# 06_MCU_Part3.net
KiCad netlist of a schematic drawn in Altium Designer
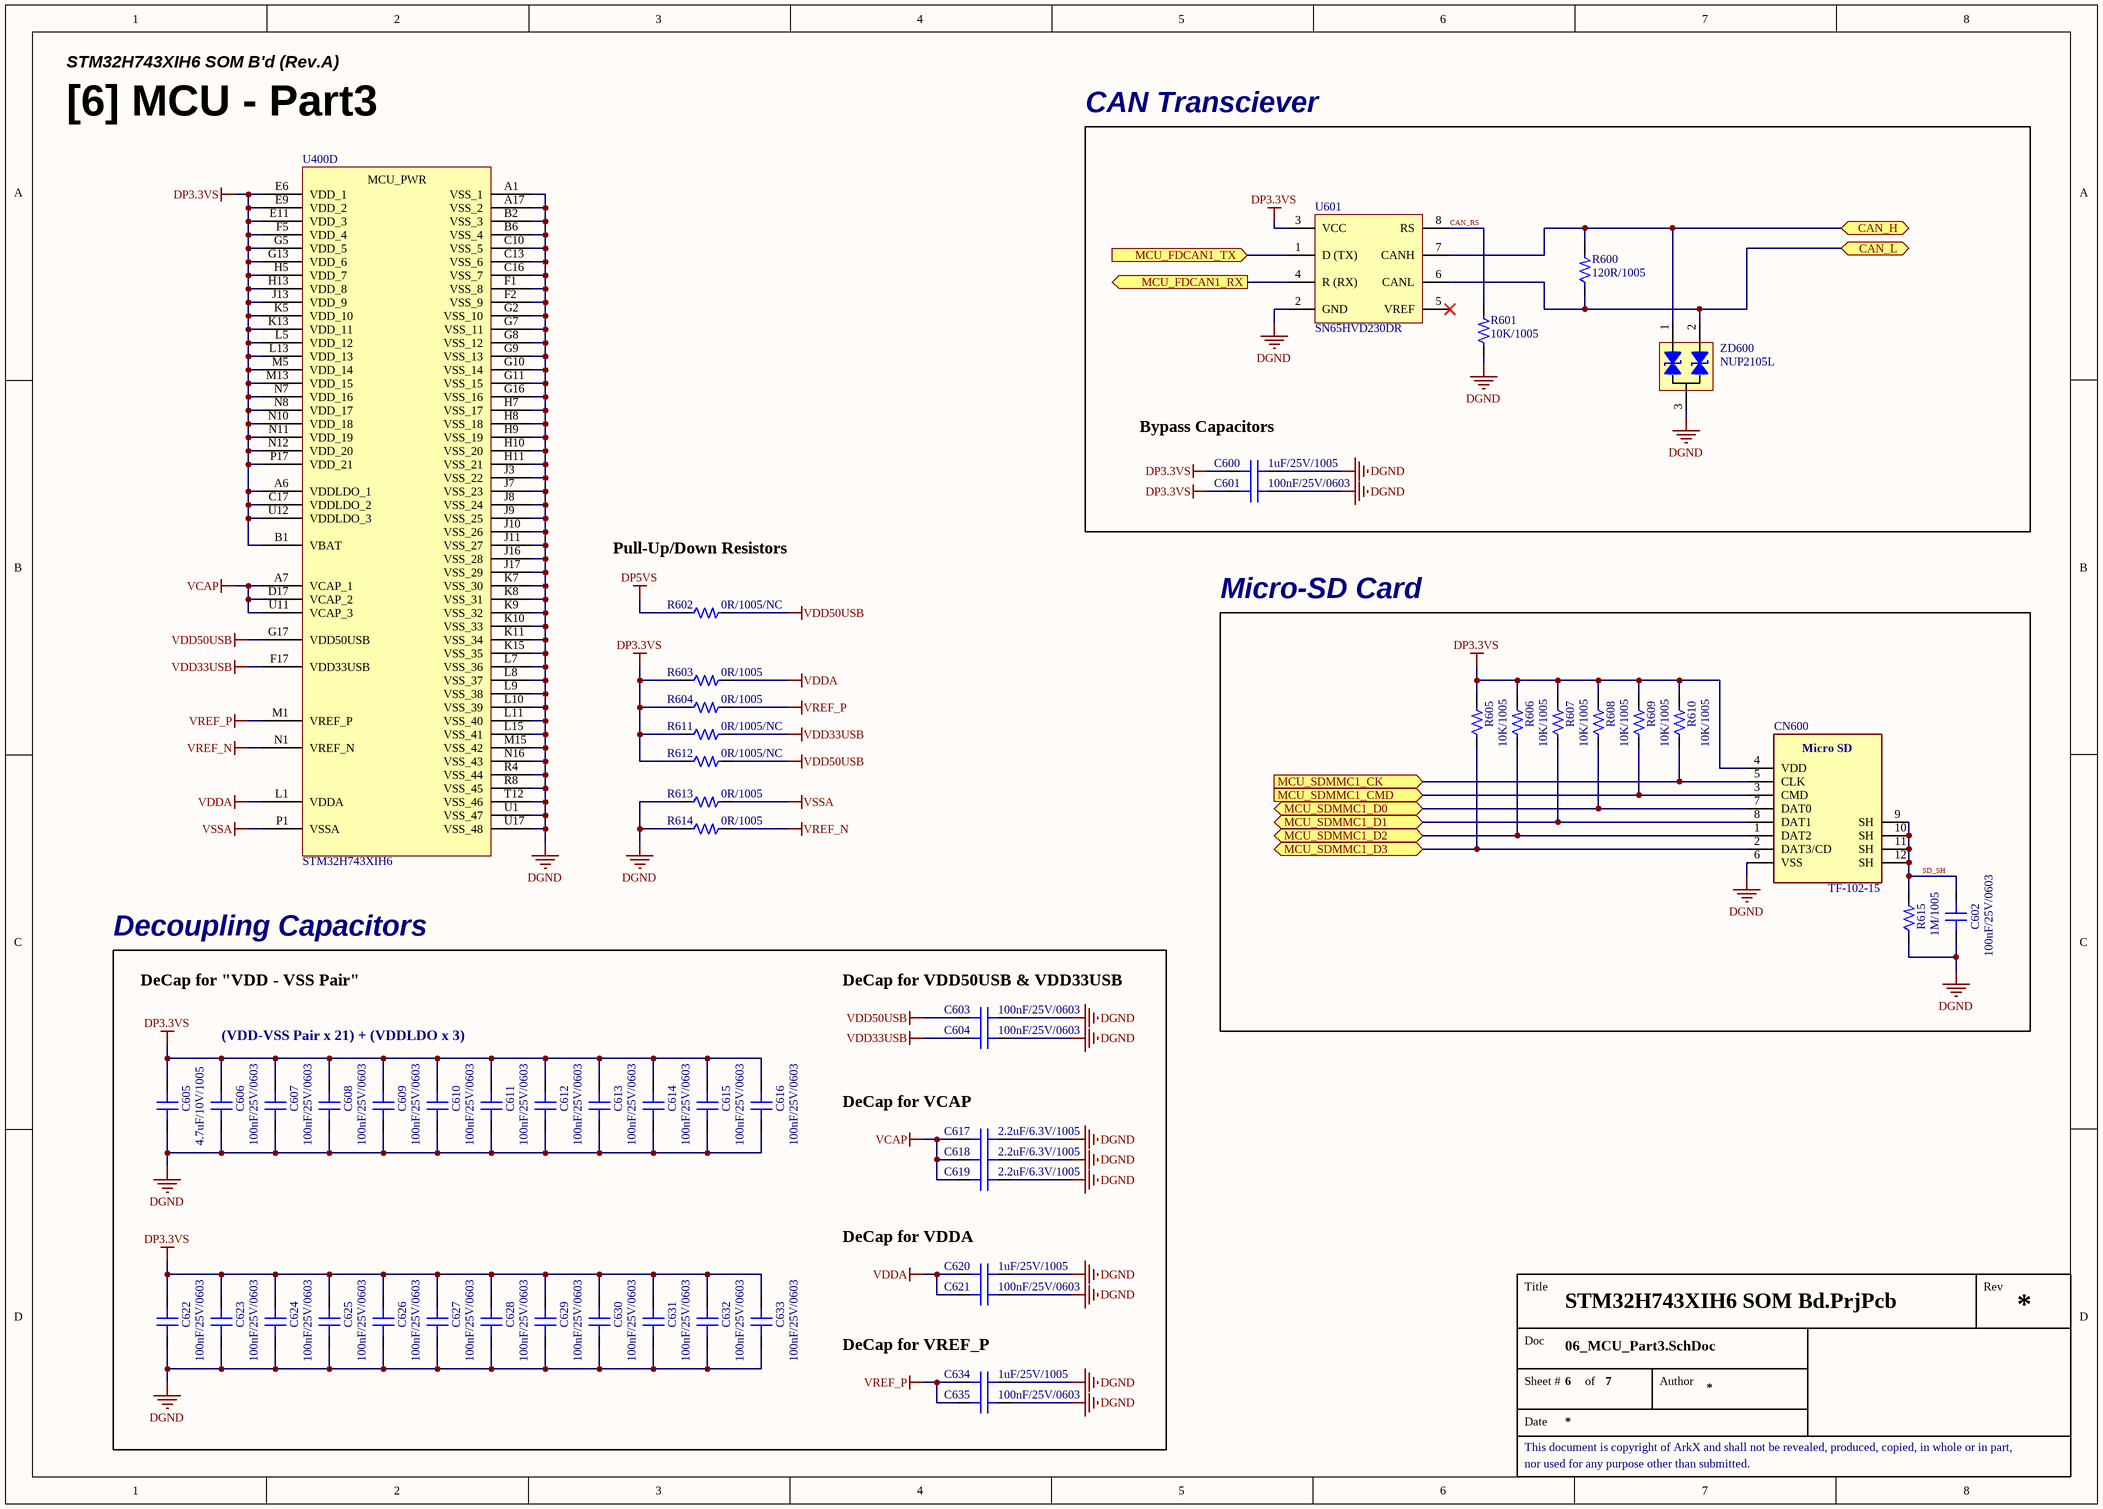
[diagram p0: 06_MCU_Part3.SchDoc]

(export (version "E")
  (design (tool "Eeschema 10.0.6"))
  (components
    (comp (ref "C600")
      (value "1uF/25V/1005")
      (footprint "CAP 1005 (0402_INCH)")
      (description "Ceramic CAP_1uF/25V/1005")
      (fields (field (name "LCSC PART #") "C52923"))
      (libsource (lib "Arkx") (part "CAP_1uF/25V/1005"))
    )
    (comp (ref "C601")
      (value "100nF/25V/0603")
      (footprint "CAP 0603 (0201_INCH)")
      (description "Ceramic CAP_100nF/25V/0603")
      (fields (field (name "LCSC PART #") "C181047"))
      (libsource (lib "Arkx") (part "CAP_100nF/25V/0603"))
    )
    (comp (ref "C602")
      (value "100nF/25V/0603")
      (footprint "CAP 0603 (0201_INCH)")
      (description "Ceramic CAP_100nF/25V/0603")
      (fields (field (name "LCSC PART #") "C181047"))
      (libsource (lib "Arkx") (part "CAP_100nF/25V/0603"))
    )
    (comp (ref "C603")
      (value "100nF/25V/0603")
      (footprint "CAP 0603 (0201_INCH)")
      (description "Ceramic CAP_100nF/25V/0603")
      (fields (field (name "LCSC PART #") "C181047"))
      (libsource (lib "Arkx") (part "CAP_100nF/25V/0603"))
    )
    (comp (ref "C604")
      (value "100nF/25V/0603")
      (footprint "CAP 0603 (0201_INCH)")
      (description "Ceramic CAP_100nF/25V/0603")
      (fields (field (name "LCSC PART #") "C181047"))
      (libsource (lib "Arkx") (part "CAP_100nF/25V/0603"))
    )
    (comp (ref "C605")
      (value "4.7uF/10V/1005")
      (footprint "CAP 1005 (0402_INCH)")
      (description "10V 4.7uF X5R ±20% 0402  Multilayer Ceramic Capacitors MLCC - SMD/SMT ROHS")
      (fields (field (name "LCSC PART #") "C23733"))
      (libsource (lib "Arkx") (part "CAP_4.7uF/10V/1005"))
    )
    (comp (ref "C606")
      (value "100nF/25V/0603")
      (footprint "CAP 0603 (0201_INCH)")
      (description "Ceramic CAP_100nF/25V/0603")
      (fields (field (name "LCSC PART #") "C181047"))
      (libsource (lib "Arkx") (part "CAP_100nF/25V/0603"))
    )
    (comp (ref "C607")
      (value "100nF/25V/0603")
      (footprint "CAP 0603 (0201_INCH)")
      (description "Ceramic CAP_100nF/25V/0603")
      (fields (field (name "LCSC PART #") "C181047"))
      (libsource (lib "Arkx") (part "CAP_100nF/25V/0603"))
    )
    (comp (ref "C608")
      (value "100nF/25V/0603")
      (footprint "CAP 0603 (0201_INCH)")
      (description "Ceramic CAP_100nF/25V/0603")
      (fields (field (name "LCSC PART #") "C181047"))
      (libsource (lib "Arkx") (part "CAP_100nF/25V/0603"))
    )
    (comp (ref "C609")
      (value "100nF/25V/0603")
      (footprint "CAP 0603 (0201_INCH)")
      (description "Ceramic CAP_100nF/25V/0603")
      (fields (field (name "LCSC PART #") "C181047"))
      (libsource (lib "Arkx") (part "CAP_100nF/25V/0603"))
    )
    (comp (ref "C610")
      (value "100nF/25V/0603")
      (footprint "CAP 0603 (0201_INCH)")
      (description "Ceramic CAP_100nF/25V/0603")
      (fields (field (name "LCSC PART #") "C181047"))
      (libsource (lib "Arkx") (part "CAP_100nF/25V/0603"))
    )
    (comp (ref "C611")
      (value "100nF/25V/0603")
      (footprint "CAP 0603 (0201_INCH)")
      (description "Ceramic CAP_100nF/25V/0603")
      (fields (field (name "LCSC PART #") "C181047"))
      (libsource (lib "Arkx") (part "CAP_100nF/25V/0603"))
    )
    (comp (ref "C612")
      (value "100nF/25V/0603")
      (footprint "CAP 0603 (0201_INCH)")
      (description "Ceramic CAP_100nF/25V/0603")
      (fields (field (name "LCSC PART #") "C181047"))
      (libsource (lib "Arkx") (part "CAP_100nF/25V/0603"))
    )
    (comp (ref "C613")
      (value "100nF/25V/0603")
      (footprint "CAP 0603 (0201_INCH)")
      (description "Ceramic CAP_100nF/25V/0603")
      (fields (field (name "LCSC PART #") "C181047"))
      (libsource (lib "Arkx") (part "CAP_100nF/25V/0603"))
    )
    (comp (ref "C614")
      (value "100nF/25V/0603")
      (footprint "CAP 0603 (0201_INCH)")
      (description "Ceramic CAP_100nF/25V/0603")
      (fields (field (name "LCSC PART #") "C181047"))
      (libsource (lib "Arkx") (part "CAP_100nF/25V/0603"))
    )
    (comp (ref "C615")
      (value "100nF/25V/0603")
      (footprint "CAP 0603 (0201_INCH)")
      (description "Ceramic CAP_100nF/25V/0603")
      (fields (field (name "LCSC PART #") "C181047"))
      (libsource (lib "Arkx") (part "CAP_100nF/25V/0603"))
    )
    (comp (ref "C616")
      (value "100nF/25V/0603")
      (footprint "CAP 0603 (0201_INCH)")
      (description "Ceramic CAP_100nF/25V/0603")
      (fields (field (name "LCSC PART #") "C181047"))
      (libsource (lib "Arkx") (part "CAP_100nF/25V/0603"))
    )
    (comp (ref "C617")
      (value "2.2uF/6.3V/1005")
      (footprint "CAP 1005 (0402_INCH)")
      (description "Ceramic CAP_2.2uF/6.3V/1005")
      (fields (field (name "LCSC PART #") "C12530"))
      (libsource (lib "Arkx") (part "CAP_2.2uF/6.3V/1005"))
    )
    (comp (ref "C618")
      (value "2.2uF/6.3V/1005")
      (footprint "CAP 1005 (0402_INCH)")
      (description "Ceramic CAP_2.2uF/6.3V/1005")
      (fields (field (name "LCSC PART #") "C12530"))
      (libsource (lib "Arkx") (part "CAP_2.2uF/6.3V/1005"))
    )
    (comp (ref "C619")
      (value "2.2uF/6.3V/1005")
      (footprint "CAP 1005 (0402_INCH)")
      (description "Ceramic CAP_2.2uF/6.3V/1005")
      (fields (field (name "LCSC PART #") "C12530"))
      (libsource (lib "Arkx") (part "CAP_2.2uF/6.3V/1005"))
    )
    (comp (ref "C620")
      (value "1uF/25V/1005")
      (footprint "CAP 1005 (0402_INCH)")
      (description "Ceramic CAP_1uF/25V/1005")
      (fields (field (name "LCSC PART #") "C52923"))
      (libsource (lib "Arkx") (part "CAP_1uF/25V/1005"))
    )
    (comp (ref "C621")
      (value "100nF/25V/0603")
      (footprint "CAP 0603 (0201_INCH)")
      (description "Ceramic CAP_100nF/25V/0603")
      (fields (field (name "LCSC PART #") "C181047"))
      (libsource (lib "Arkx") (part "CAP_100nF/25V/0603"))
    )
    (comp (ref "C622")
      (value "100nF/25V/0603")
      (footprint "CAP 0603 (0201_INCH)")
      (description "Ceramic CAP_100nF/25V/0603")
      (fields (field (name "LCSC PART #") "C181047"))
      (libsource (lib "Arkx") (part "CAP_100nF/25V/0603"))
    )
    (comp (ref "C623")
      (value "100nF/25V/0603")
      (footprint "CAP 0603 (0201_INCH)")
      (description "Ceramic CAP_100nF/25V/0603")
      (fields (field (name "LCSC PART #") "C181047"))
      (libsource (lib "Arkx") (part "CAP_100nF/25V/0603"))
    )
    (comp (ref "C624")
      (value "100nF/25V/0603")
      (footprint "CAP 0603 (0201_INCH)")
      (description "Ceramic CAP_100nF/25V/0603")
      (fields (field (name "LCSC PART #") "C181047"))
      (libsource (lib "Arkx") (part "CAP_100nF/25V/0603"))
    )
    (comp (ref "C625")
      (value "100nF/25V/0603")
      (footprint "CAP 0603 (0201_INCH)")
      (description "Ceramic CAP_100nF/25V/0603")
      (fields (field (name "LCSC PART #") "C181047"))
      (libsource (lib "Arkx") (part "CAP_100nF/25V/0603"))
    )
    (comp (ref "C626")
      (value "100nF/25V/0603")
      (footprint "CAP 0603 (0201_INCH)")
      (description "Ceramic CAP_100nF/25V/0603")
      (fields (field (name "LCSC PART #") "C181047"))
      (libsource (lib "Arkx") (part "CAP_100nF/25V/0603"))
    )
    (comp (ref "C627")
      (value "100nF/25V/0603")
      (footprint "CAP 0603 (0201_INCH)")
      (description "Ceramic CAP_100nF/25V/0603")
      (fields (field (name "LCSC PART #") "C181047"))
      (libsource (lib "Arkx") (part "CAP_100nF/25V/0603"))
    )
    (comp (ref "C628")
      (value "100nF/25V/0603")
      (footprint "CAP 0603 (0201_INCH)")
      (description "Ceramic CAP_100nF/25V/0603")
      (fields (field (name "LCSC PART #") "C181047"))
      (libsource (lib "Arkx") (part "CAP_100nF/25V/0603"))
    )
    (comp (ref "C629")
      (value "100nF/25V/0603")
      (footprint "CAP 0603 (0201_INCH)")
      (description "Ceramic CAP_100nF/25V/0603")
      (fields (field (name "LCSC PART #") "C181047"))
      (libsource (lib "Arkx") (part "CAP_100nF/25V/0603"))
    )
    (comp (ref "C630")
      (value "100nF/25V/0603")
      (footprint "CAP 0603 (0201_INCH)")
      (description "Ceramic CAP_100nF/25V/0603")
      (fields (field (name "LCSC PART #") "C181047"))
      (libsource (lib "Arkx") (part "CAP_100nF/25V/0603"))
    )
    (comp (ref "C631")
      (value "100nF/25V/0603")
      (footprint "CAP 0603 (0201_INCH)")
      (description "Ceramic CAP_100nF/25V/0603")
      (fields (field (name "LCSC PART #") "C181047"))
      (libsource (lib "Arkx") (part "CAP_100nF/25V/0603"))
    )
    (comp (ref "C632")
      (value "100nF/25V/0603")
      (footprint "CAP 0603 (0201_INCH)")
      (description "Ceramic CAP_100nF/25V/0603")
      (fields (field (name "LCSC PART #") "C181047"))
      (libsource (lib "Arkx") (part "CAP_100nF/25V/0603"))
    )
    (comp (ref "C633")
      (value "100nF/25V/0603")
      (footprint "CAP 0603 (0201_INCH)")
      (description "Ceramic CAP_100nF/25V/0603")
      (fields (field (name "LCSC PART #") "C181047"))
      (libsource (lib "Arkx") (part "CAP_100nF/25V/0603"))
    )
    (comp (ref "C634")
      (value "1uF/25V/1005")
      (footprint "CAP 1005 (0402_INCH)")
      (description "Ceramic CAP_1uF/25V/1005")
      (fields (field (name "LCSC PART #") "C52923"))
      (libsource (lib "Arkx") (part "CAP_1uF/25V/1005"))
    )
    (comp (ref "C635")
      (value "100nF/25V/0603")
      (footprint "CAP 0603 (0201_INCH)")
      (description "Ceramic CAP_100nF/25V/0603")
      (fields (field (name "LCSC PART #") "C181047"))
      (libsource (lib "Arkx") (part "CAP_100nF/25V/0603"))
    )
    (comp (ref "CN600")
      (value "TF-102-15")
      (footprint "CON_MICRO-SD_Socket_TF-102-15")
      (fields (field (name "LCSC PART #") "C266609"))
      (libsource (lib "Arkx") (part "CON_MICRO-SD_Socket_TF-102-15"))
    )
    (comp (ref "R600")
      (value "120R/1005")
      (footprint "RES 1005 (0402_inch)")
      (description "RES_120R/1005/62.5mW")
      (fields (field (name "LCSC PART #") "C25079"))
      (libsource (lib "Arkx") (part "RES_120R/1005/62.5mW"))
    )
    (comp (ref "R601")
      (value "10K/1005")
      (footprint "RES 1005 (0402_inch)")
      (description "RES_10K/1005/62.5mW")
      (fields (field (name "LCSC PART #") "C25744"))
      (libsource (lib "Arkx") (part "RES_10K/1005/62.5mW"))
    )
    (comp (ref "R602")
      (value "0R/1005/NC")
      (footprint "RES 1005 (0402_inch)/NC")
      (description "RES_0R/1005/62.5mW/NC")
      (libsource (lib "Arkx") (part "RES_NC_0R/1005/62.5mW"))
    )
    (comp (ref "R603")
      (value "0R/1005")
      (footprint "RES 1005 (0402_inch)")
      (description "RES_0R/1005/62.5mW")
      (fields (field (name "LCSC PART #") "C17168"))
      (libsource (lib "Arkx") (part "RES_0R/1005/62.5mW"))
    )
    (comp (ref "R604")
      (value "0R/1005")
      (footprint "RES 1005 (0402_inch)")
      (description "RES_0R/1005/62.5mW")
      (fields (field (name "LCSC PART #") "C17168"))
      (libsource (lib "Arkx") (part "RES_0R/1005/62.5mW"))
    )
    (comp (ref "R605")
      (value "10K/1005")
      (footprint "RES 1005 (0402_inch)")
      (description "RES_10K/1005/62.5mW")
      (fields (field (name "LCSC PART #") "C25744"))
      (libsource (lib "Arkx") (part "RES_10K/1005/62.5mW"))
    )
    (comp (ref "R606")
      (value "10K/1005")
      (footprint "RES 1005 (0402_inch)")
      (description "RES_10K/1005/62.5mW")
      (fields (field (name "LCSC PART #") "C25744"))
      (libsource (lib "Arkx") (part "RES_10K/1005/62.5mW"))
    )
    (comp (ref "R607")
      (value "10K/1005")
      (footprint "RES 1005 (0402_inch)")
      (description "RES_10K/1005/62.5mW")
      (fields (field (name "LCSC PART #") "C25744"))
      (libsource (lib "Arkx") (part "RES_10K/1005/62.5mW"))
    )
    (comp (ref "R608")
      (value "10K/1005")
      (footprint "RES 1005 (0402_inch)")
      (description "RES_10K/1005/62.5mW")
      (fields (field (name "LCSC PART #") "C25744"))
      (libsource (lib "Arkx") (part "RES_10K/1005/62.5mW"))
    )
    (comp (ref "R609")
      (value "10K/1005")
      (footprint "RES 1005 (0402_inch)")
      (description "RES_10K/1005/62.5mW")
      (fields (field (name "LCSC PART #") "C25744"))
      (libsource (lib "Arkx") (part "RES_10K/1005/62.5mW"))
    )
    (comp (ref "R610")
      (value "10K/1005")
      (footprint "RES 1005 (0402_inch)")
      (description "RES_10K/1005/62.5mW")
      (fields (field (name "LCSC PART #") "C25744"))
      (libsource (lib "Arkx") (part "RES_10K/1005/62.5mW"))
    )
    (comp (ref "R611")
      (value "0R/1005/NC")
      (footprint "RES 1005 (0402_inch)/NC")
      (description "RES_0R/1005/62.5mW/NC")
      (libsource (lib "Arkx") (part "RES_NC_0R/1005/62.5mW"))
    )
    (comp (ref "R612")
      (value "0R/1005/NC")
      (footprint "RES 1005 (0402_inch)/NC")
      (description "RES_0R/1005/62.5mW/NC")
      (libsource (lib "Arkx") (part "RES_NC_0R/1005/62.5mW"))
    )
    (comp (ref "R613")
      (value "0R/1005")
      (footprint "RES 1005 (0402_inch)")
      (description "RES_0R/1005/62.5mW")
      (fields (field (name "LCSC PART #") "C17168"))
      (libsource (lib "Arkx") (part "RES_0R/1005/62.5mW"))
    )
    (comp (ref "R614")
      (value "0R/1005")
      (footprint "RES 1005 (0402_inch)")
      (description "RES_0R/1005/62.5mW")
      (fields (field (name "LCSC PART #") "C17168"))
      (libsource (lib "Arkx") (part "RES_0R/1005/62.5mW"))
    )
    (comp (ref "R615")
      (value "1M/1005")
      (footprint "RES 1005 (0402_inch)")
      (description "RES_1M/1005/62.5mW")
      (fields (field (name "LCSC PART #") "C26083"))
      (libsource (lib "Arkx") (part "RES_1M/1005/62.5mW"))
    )
    (comp (ref "U400")
      (value "STM32H743XIH6")
      (footprint "IC TFBGA-265")
      (description "ARM® Cortex®-M7 STM32H7 MCU IC 32bit Single-core 480MHz 2MB(2M x 8) Flash 240+25-TFBGA(14x14)")
      (fields (field (name "LCSC PART #") "C114407"))
      (libsource (lib "Arkx") (part "IC_MCU_STM32H743XIH6"))
    )
    (comp (ref "U601")
      (value "SN65HVD230DR")
      (footprint "SOIC-8 R8 (ANALOG DEV)")
      (description "IC TRANSCEIVER HALF 1/1 8SOIC")
      (fields (field (name "LCSC PART #") "C12084"))
      (libsource (lib "Arkx") (part "IC_CAN_SN65HVD230DR"))
    )
    (comp (ref "ZD600")
      (value "NUP2105L")
      (footprint "SOT 23-3 (DIODES INCORPORATED)")
      (description "SOT-23 ESD PROTECTION DEVICES RO")
      (fields (field (name "LCSC PART #") "C5158054"))
      (libsource (lib "Arkx") (part "DIO_TVS_NUP2105L"))
    )
  )
  (nets
    (net (code "1") (name "/CAN_H") (class "Default")
      (node (ref "R600") (pin "2") (pinfunction "2_2") (pintype "passive"))
      (node (ref "U601") (pin "7") (pinfunction "CANH_7") (pintype "passive"))
      (node (ref "ZD600") (pin "1") (pinfunction "CANH_1") (pintype "passive"))
    )
    (net (code "2") (name "/CAN_L") (class "Default")
      (node (ref "R600") (pin "1") (pinfunction "1_1") (pintype "passive"))
      (node (ref "U601") (pin "6") (pinfunction "CANL_6") (pintype "passive"))
      (node (ref "ZD600") (pin "2") (pinfunction "CANL_2") (pintype "passive"))
    )
    (net (code "3") (name "/CAN_RS") (class "Default")
      (node (ref "R601") (pin "2") (pinfunction "2_2") (pintype "passive"))
      (node (ref "U601") (pin "8") (pinfunction "RS_8") (pintype "passive"))
    )
    (net (code "4") (name "/MCU_FDCAN1_RX") (class "Default")
      (node (ref "U601") (pin "4") (pinfunction "R_(RX)_4") (pintype "passive"))
    )
    (net (code "5") (name "/MCU_FDCAN1_TX") (class "Default")
      (node (ref "U601") (pin "1") (pinfunction "D_(TX)_1") (pintype "passive"))
    )
    (net (code "6") (name "/MCU_SDMMC1_CK") (class "Default")
      (node (ref "CN600") (pin "5") (pinfunction "CLK_5") (pintype "passive"))
      (node (ref "R610") (pin "1") (pinfunction "1_1") (pintype "passive"))
    )
    (net (code "7") (name "/MCU_SDMMC1_CMD") (class "Default")
      (node (ref "CN600") (pin "3") (pinfunction "CMD_3") (pintype "passive"))
      (node (ref "R609") (pin "1") (pinfunction "1_1") (pintype "passive"))
    )
    (net (code "8") (name "/MCU_SDMMC1_D0") (class "Default")
      (node (ref "CN600") (pin "7") (pinfunction "DAT0_7") (pintype "passive"))
      (node (ref "R608") (pin "1") (pinfunction "1_1") (pintype "passive"))
    )
    (net (code "9") (name "/MCU_SDMMC1_D1") (class "Default")
      (node (ref "CN600") (pin "8") (pinfunction "DAT1_8") (pintype "passive"))
      (node (ref "R607") (pin "1") (pinfunction "1_1") (pintype "passive"))
    )
    (net (code "10") (name "/MCU_SDMMC1_D2") (class "Default")
      (node (ref "CN600") (pin "1") (pinfunction "DAT2_1") (pintype "passive"))
      (node (ref "R606") (pin "1") (pinfunction "1_1") (pintype "passive"))
    )
    (net (code "11") (name "/MCU_SDMMC1_D3") (class "Default")
      (node (ref "CN600") (pin "2") (pinfunction "DAT3/CD_2") (pintype "passive"))
      (node (ref "R605") (pin "1") (pinfunction "1_1") (pintype "passive"))
    )
    (net (code "12") (name "/SD_SH") (class "Default")
      (node (ref "C602") (pin "1") (pinfunction "1_1") (pintype "passive"))
      (node (ref "CN600") (pin "10") (pinfunction "SH_10") (pintype "passive"))
      (node (ref "CN600") (pin "11") (pinfunction "SH_11") (pintype "passive"))
      (node (ref "CN600") (pin "12") (pinfunction "SH_12") (pintype "passive"))
      (node (ref "CN600") (pin "9") (pinfunction "SH_9") (pintype "passive"))
      (node (ref "R615") (pin "2") (pinfunction "2_2") (pintype "passive"))
    )
    (net (code "13") (name "DGND") (class "Default")
      (node (ref "C600") (pin "2") (pinfunction "2_2") (pintype "passive"))
      (node (ref "C601") (pin "1") (pinfunction "1_1") (pintype "passive"))
      (node (ref "C602") (pin "2") (pinfunction "2_2") (pintype "passive"))
      (node (ref "C603") (pin "1") (pinfunction "1_1") (pintype "passive"))
      (node (ref "C604") (pin "1") (pinfunction "1_1") (pintype "passive"))
      (node (ref "C605") (pin "1") (pinfunction "1_1") (pintype "passive"))
      (node (ref "C606") (pin "1") (pinfunction "1_1") (pintype "passive"))
      (node (ref "C607") (pin "1") (pinfunction "1_1") (pintype "passive"))
      (node (ref "C608") (pin "1") (pinfunction "1_1") (pintype "passive"))
      (node (ref "C609") (pin "1") (pinfunction "1_1") (pintype "passive"))
      (node (ref "C610") (pin "1") (pinfunction "1_1") (pintype "passive"))
      (node (ref "C611") (pin "1") (pinfunction "1_1") (pintype "passive"))
      (node (ref "C612") (pin "1") (pinfunction "1_1") (pintype "passive"))
      (node (ref "C613") (pin "1") (pinfunction "1_1") (pintype "passive"))
      (node (ref "C614") (pin "1") (pinfunction "1_1") (pintype "passive"))
      (node (ref "C615") (pin "1") (pinfunction "1_1") (pintype "passive"))
      (node (ref "C616") (pin "1") (pinfunction "1_1") (pintype "passive"))
      (node (ref "C617") (pin "2") (pinfunction "2_2") (pintype "passive"))
      (node (ref "C618") (pin "2") (pinfunction "2_2") (pintype "passive"))
      (node (ref "C619") (pin "2") (pinfunction "2_2") (pintype "passive"))
      (node (ref "C620") (pin "2") (pinfunction "2_2") (pintype "passive"))
      (node (ref "C621") (pin "1") (pinfunction "1_1") (pintype "passive"))
      (node (ref "C622") (pin "1") (pinfunction "1_1") (pintype "passive"))
      (node (ref "C623") (pin "1") (pinfunction "1_1") (pintype "passive"))
      (node (ref "C624") (pin "1") (pinfunction "1_1") (pintype "passive"))
      (node (ref "C625") (pin "1") (pinfunction "1_1") (pintype "passive"))
      (node (ref "C626") (pin "1") (pinfunction "1_1") (pintype "passive"))
      (node (ref "C627") (pin "1") (pinfunction "1_1") (pintype "passive"))
      (node (ref "C628") (pin "1") (pinfunction "1_1") (pintype "passive"))
      (node (ref "C629") (pin "1") (pinfunction "1_1") (pintype "passive"))
      (node (ref "C630") (pin "1") (pinfunction "1_1") (pintype "passive"))
      (node (ref "C631") (pin "1") (pinfunction "1_1") (pintype "passive"))
      (node (ref "C632") (pin "1") (pinfunction "1_1") (pintype "passive"))
      (node (ref "C633") (pin "1") (pinfunction "1_1") (pintype "passive"))
      (node (ref "C634") (pin "2") (pinfunction "2_2") (pintype "passive"))
      (node (ref "C635") (pin "1") (pinfunction "1_1") (pintype "passive"))
      (node (ref "CN600") (pin "6") (pinfunction "VSS_6") (pintype "passive"))
      (node (ref "R601") (pin "1") (pinfunction "1_1") (pintype "passive"))
      (node (ref "R613") (pin "1") (pinfunction "1_1") (pintype "passive"))
      (node (ref "R614") (pin "1") (pinfunction "1_1") (pintype "passive"))
      (node (ref "R615") (pin "1") (pinfunction "1_1") (pintype "passive"))
      (node (ref "U400") (pin "A1") (pinfunction "VSS_1_A1") (pintype "passive"))
      (node (ref "U400") (pin "A17") (pinfunction "VSS_2_A17") (pintype "passive"))
      (node (ref "U400") (pin "B2") (pinfunction "VSS_3_B2") (pintype "passive"))
      (node (ref "U400") (pin "B6") (pinfunction "VSS_4_B6") (pintype "passive"))
      (node (ref "U400") (pin "C10") (pinfunction "VSS_5_C10") (pintype "passive"))
      (node (ref "U400") (pin "C13") (pinfunction "VSS_6_C13") (pintype "passive"))
      (node (ref "U400") (pin "C16") (pinfunction "VSS_7_C16") (pintype "passive"))
      (node (ref "U400") (pin "F1") (pinfunction "VSS_8_F1") (pintype "passive"))
      (node (ref "U400") (pin "F2") (pinfunction "VSS_9_F2") (pintype "passive"))
      (node (ref "U400") (pin "G10") (pinfunction "VSS_14_G10") (pintype "passive"))
      (node (ref "U400") (pin "G11") (pinfunction "VSS_15_G11") (pintype "passive"))
      (node (ref "U400") (pin "G16") (pinfunction "VSS_16_G16") (pintype "passive"))
      (node (ref "U400") (pin "G2") (pinfunction "VSS_10_G2") (pintype "passive"))
      (node (ref "U400") (pin "G7") (pinfunction "VSS_11_G7") (pintype "passive"))
      (node (ref "U400") (pin "G8") (pinfunction "VSS_12_G8") (pintype "passive"))
      (node (ref "U400") (pin "G9") (pinfunction "VSS_13_G9") (pintype "passive"))
      (node (ref "U400") (pin "H10") (pinfunction "VSS_20_H10") (pintype "passive"))
      (node (ref "U400") (pin "H11") (pinfunction "VSS_21_H11") (pintype "passive"))
      (node (ref "U400") (pin "H7") (pinfunction "VSS_17_H7") (pintype "passive"))
      (node (ref "U400") (pin "H8") (pinfunction "VSS_18_H8") (pintype "passive"))
      (node (ref "U400") (pin "H9") (pinfunction "VSS_19_H9") (pintype "passive"))
      (node (ref "U400") (pin "J10") (pinfunction "VSS_26_J10") (pintype "passive"))
      (node (ref "U400") (pin "J11") (pinfunction "VSS_27_J11") (pintype "passive"))
      (node (ref "U400") (pin "J16") (pinfunction "VSS_28_J16") (pintype "passive"))
      (node (ref "U400") (pin "J17") (pinfunction "VSS_29_J17") (pintype "passive"))
      (node (ref "U400") (pin "J3") (pinfunction "VSS_22_J3") (pintype "passive"))
      (node (ref "U400") (pin "J7") (pinfunction "VSS_23_J7") (pintype "passive"))
      (node (ref "U400") (pin "J8") (pinfunction "VSS_24_J8") (pintype "passive"))
      (node (ref "U400") (pin "J9") (pinfunction "VSS_25_J9") (pintype "passive"))
      (node (ref "U400") (pin "K10") (pinfunction "VSS_33_K10") (pintype "passive"))
      (node (ref "U400") (pin "K11") (pinfunction "VSS_34_K11") (pintype "passive"))
      (node (ref "U400") (pin "K15") (pinfunction "VSS_35_K15") (pintype "passive"))
      (node (ref "U400") (pin "K7") (pinfunction "VSS_30_K7") (pintype "passive"))
      (node (ref "U400") (pin "K8") (pinfunction "VSS_31_K8") (pintype "passive"))
      (node (ref "U400") (pin "K9") (pinfunction "VSS_32_K9") (pintype "passive"))
      (node (ref "U400") (pin "L10") (pinfunction "VSS_39_L10") (pintype "passive"))
      (node (ref "U400") (pin "L11") (pinfunction "VSS_40_L11") (pintype "passive"))
      (node (ref "U400") (pin "L15") (pinfunction "VSS_41_L15") (pintype "passive"))
      (node (ref "U400") (pin "L7") (pinfunction "VSS_36_L7") (pintype "passive"))
      (node (ref "U400") (pin "L8") (pinfunction "VSS_37_L8") (pintype "passive"))
      (node (ref "U400") (pin "L9") (pinfunction "VSS_38_L9") (pintype "passive"))
      (node (ref "U400") (pin "M15") (pinfunction "VSS_42_M15") (pintype "passive"))
      (node (ref "U400") (pin "N16") (pinfunction "VSS_43_N16") (pintype "passive"))
      (node (ref "U400") (pin "R4") (pinfunction "VSS_44_R4") (pintype "passive"))
      (node (ref "U400") (pin "R8") (pinfunction "VSS_45_R8") (pintype "passive"))
      (node (ref "U400") (pin "T12") (pinfunction "VSS_46_T12") (pintype "passive"))
      (node (ref "U400") (pin "U1") (pinfunction "VSS_47_U1") (pintype "passive"))
      (node (ref "U400") (pin "U17") (pinfunction "VSS_48_U17") (pintype "passive"))
      (node (ref "U601") (pin "2") (pinfunction "GND_2") (pintype "passive"))
      (node (ref "ZD600") (pin "3") (pinfunction "GND_3") (pintype "passive"))
    )
    (net (code "14") (name "DP3.3VS") (class "Default")
      (node (ref "C600") (pin "1") (pinfunction "1_1") (pintype "passive"))
      (node (ref "C601") (pin "2") (pinfunction "2_2") (pintype "passive"))
      (node (ref "C605") (pin "2") (pinfunction "2_2") (pintype "passive"))
      (node (ref "C606") (pin "2") (pinfunction "2_2") (pintype "passive"))
      (node (ref "C607") (pin "2") (pinfunction "2_2") (pintype "passive"))
      (node (ref "C608") (pin "2") (pinfunction "2_2") (pintype "passive"))
      (node (ref "C609") (pin "2") (pinfunction "2_2") (pintype "passive"))
      (node (ref "C610") (pin "2") (pinfunction "2_2") (pintype "passive"))
      (node (ref "C611") (pin "2") (pinfunction "2_2") (pintype "passive"))
      (node (ref "C612") (pin "2") (pinfunction "2_2") (pintype "passive"))
      (node (ref "C613") (pin "2") (pinfunction "2_2") (pintype "passive"))
      (node (ref "C614") (pin "2") (pinfunction "2_2") (pintype "passive"))
      (node (ref "C615") (pin "2") (pinfunction "2_2") (pintype "passive"))
      (node (ref "C616") (pin "2") (pinfunction "2_2") (pintype "passive"))
      (node (ref "C622") (pin "2") (pinfunction "2_2") (pintype "passive"))
      (node (ref "C623") (pin "2") (pinfunction "2_2") (pintype "passive"))
      (node (ref "C624") (pin "2") (pinfunction "2_2") (pintype "passive"))
      (node (ref "C625") (pin "2") (pinfunction "2_2") (pintype "passive"))
      (node (ref "C626") (pin "2") (pinfunction "2_2") (pintype "passive"))
      (node (ref "C627") (pin "2") (pinfunction "2_2") (pintype "passive"))
      (node (ref "C628") (pin "2") (pinfunction "2_2") (pintype "passive"))
      (node (ref "C629") (pin "2") (pinfunction "2_2") (pintype "passive"))
      (node (ref "C630") (pin "2") (pinfunction "2_2") (pintype "passive"))
      (node (ref "C631") (pin "2") (pinfunction "2_2") (pintype "passive"))
      (node (ref "C632") (pin "2") (pinfunction "2_2") (pintype "passive"))
      (node (ref "C633") (pin "2") (pinfunction "2_2") (pintype "passive"))
      (node (ref "CN600") (pin "4") (pinfunction "VDD_4") (pintype "passive"))
      (node (ref "R603") (pin "1") (pinfunction "1_1") (pintype "passive"))
      (node (ref "R604") (pin "1") (pinfunction "1_1") (pintype "passive"))
      (node (ref "R605") (pin "2") (pinfunction "2_2") (pintype "passive"))
      (node (ref "R606") (pin "2") (pinfunction "2_2") (pintype "passive"))
      (node (ref "R607") (pin "2") (pinfunction "2_2") (pintype "passive"))
      (node (ref "R608") (pin "2") (pinfunction "2_2") (pintype "passive"))
      (node (ref "R609") (pin "2") (pinfunction "2_2") (pintype "passive"))
      (node (ref "R610") (pin "2") (pinfunction "2_2") (pintype "passive"))
      (node (ref "R611") (pin "1") (pinfunction "1_1") (pintype "passive"))
      (node (ref "R612") (pin "1") (pinfunction "1_1") (pintype "passive"))
      (node (ref "U400") (pin "A6") (pinfunction "VDDLDO_1_A6") (pintype "passive"))
      (node (ref "U400") (pin "B1") (pinfunction "VBAT_B1") (pintype "passive"))
      (node (ref "U400") (pin "C17") (pinfunction "VDDLDO_2_C17") (pintype "passive"))
      (node (ref "U400") (pin "E11") (pinfunction "VDD_3_E11") (pintype "passive"))
      (node (ref "U400") (pin "E6") (pinfunction "VDD_1_E6") (pintype "passive"))
      (node (ref "U400") (pin "E9") (pinfunction "VDD_2_E9") (pintype "passive"))
      (node (ref "U400") (pin "F5") (pinfunction "VDD_4_F5") (pintype "passive"))
      (node (ref "U400") (pin "G13") (pinfunction "VDD_6_G13") (pintype "passive"))
      (node (ref "U400") (pin "G5") (pinfunction "VDD_5_G5") (pintype "passive"))
      (node (ref "U400") (pin "H13") (pinfunction "VDD_8_H13") (pintype "passive"))
      (node (ref "U400") (pin "H5") (pinfunction "VDD_7_H5") (pintype "passive"))
      (node (ref "U400") (pin "J13") (pinfunction "VDD_9_J13") (pintype "passive"))
      (node (ref "U400") (pin "K13") (pinfunction "VDD_11_K13") (pintype "passive"))
      (node (ref "U400") (pin "K5") (pinfunction "VDD_10_K5") (pintype "passive"))
      (node (ref "U400") (pin "L13") (pinfunction "VDD_13_L13") (pintype "passive"))
      (node (ref "U400") (pin "L5") (pinfunction "VDD_12_L5") (pintype "passive"))
      (node (ref "U400") (pin "M13") (pinfunction "VDD_15_M13") (pintype "passive"))
      (node (ref "U400") (pin "M5") (pinfunction "VDD_14_M5") (pintype "passive"))
      (node (ref "U400") (pin "N10") (pinfunction "VDD_18_N10") (pintype "passive"))
      (node (ref "U400") (pin "N11") (pinfunction "VDD_19_N11") (pintype "passive"))
      (node (ref "U400") (pin "N12") (pinfunction "VDD_20_N12") (pintype "passive"))
      (node (ref "U400") (pin "N7") (pinfunction "VDD_16_N7") (pintype "passive"))
      (node (ref "U400") (pin "N8") (pinfunction "VDD_17_N8") (pintype "passive"))
      (node (ref "U400") (pin "P17") (pinfunction "VDD_21_P17") (pintype "passive"))
      (node (ref "U400") (pin "U12") (pinfunction "VDDLDO_3_U12") (pintype "passive"))
      (node (ref "U601") (pin "3") (pinfunction "VCC_3") (pintype "passive"))
    )
    (net (code "15") (name "DP5VS") (class "Default")
      (node (ref "R602") (pin "1") (pinfunction "1_1") (pintype "passive"))
    )
    (net (code "16") (name "VCAP") (class "Default")
      (node (ref "C617") (pin "1") (pinfunction "1_1") (pintype "passive"))
      (node (ref "C618") (pin "1") (pinfunction "1_1") (pintype "passive"))
      (node (ref "C619") (pin "1") (pinfunction "1_1") (pintype "passive"))
      (node (ref "U400") (pin "A7") (pinfunction "VCAP_1_A7") (pintype "passive"))
      (node (ref "U400") (pin "D17") (pinfunction "VCAP_2_D17") (pintype "passive"))
      (node (ref "U400") (pin "U11") (pinfunction "VCAP_3_U11") (pintype "passive"))
    )
    (net (code "17") (name "VDD33USB") (class "Default")
      (node (ref "C604") (pin "2") (pinfunction "2_2") (pintype "passive"))
      (node (ref "R611") (pin "2") (pinfunction "2_2") (pintype "passive"))
      (node (ref "U400") (pin "F17") (pinfunction "VDD33USB_F17") (pintype "passive"))
    )
    (net (code "18") (name "VDD50USB") (class "Default")
      (node (ref "C603") (pin "2") (pinfunction "2_2") (pintype "passive"))
      (node (ref "R602") (pin "2") (pinfunction "2_2") (pintype "passive"))
      (node (ref "R612") (pin "2") (pinfunction "2_2") (pintype "passive"))
      (node (ref "U400") (pin "G17") (pinfunction "VDD50USB_G17") (pintype "passive"))
    )
    (net (code "19") (name "VDDA") (class "Default")
      (node (ref "C620") (pin "1") (pinfunction "1_1") (pintype "passive"))
      (node (ref "C621") (pin "2") (pinfunction "2_2") (pintype "passive"))
      (node (ref "R603") (pin "2") (pinfunction "2_2") (pintype "passive"))
      (node (ref "U400") (pin "L1") (pinfunction "VDDA_L1") (pintype "passive"))
    )
    (net (code "20") (name "VREF_N") (class "Default")
      (node (ref "R614") (pin "2") (pinfunction "2_2") (pintype "passive"))
      (node (ref "U400") (pin "N1") (pinfunction "VREF_N_N1") (pintype "passive"))
    )
    (net (code "21") (name "VREF_P") (class "Default")
      (node (ref "C634") (pin "1") (pinfunction "1_1") (pintype "passive"))
      (node (ref "C635") (pin "2") (pinfunction "2_2") (pintype "passive"))
      (node (ref "R604") (pin "2") (pinfunction "2_2") (pintype "passive"))
      (node (ref "U400") (pin "M1") (pinfunction "VREF_P_M1") (pintype "passive"))
    )
    (net (code "22") (name "VSSA") (class "Default")
      (node (ref "R613") (pin "2") (pinfunction "2_2") (pintype "passive"))
      (node (ref "U400") (pin "P1") (pinfunction "VSSA_P1") (pintype "passive"))
    )
    (net (code "23") (name "unconnected-(U601-VREF-Pad5)") (class "Default")
      (node (ref "U601") (pin "5") (pinfunction "VREF_5") (pintype "passive+no_connect"))
    )
  )
)
